# Ivy_Sensor.net
KiCad netlist of a schematic drawn in EAGLE
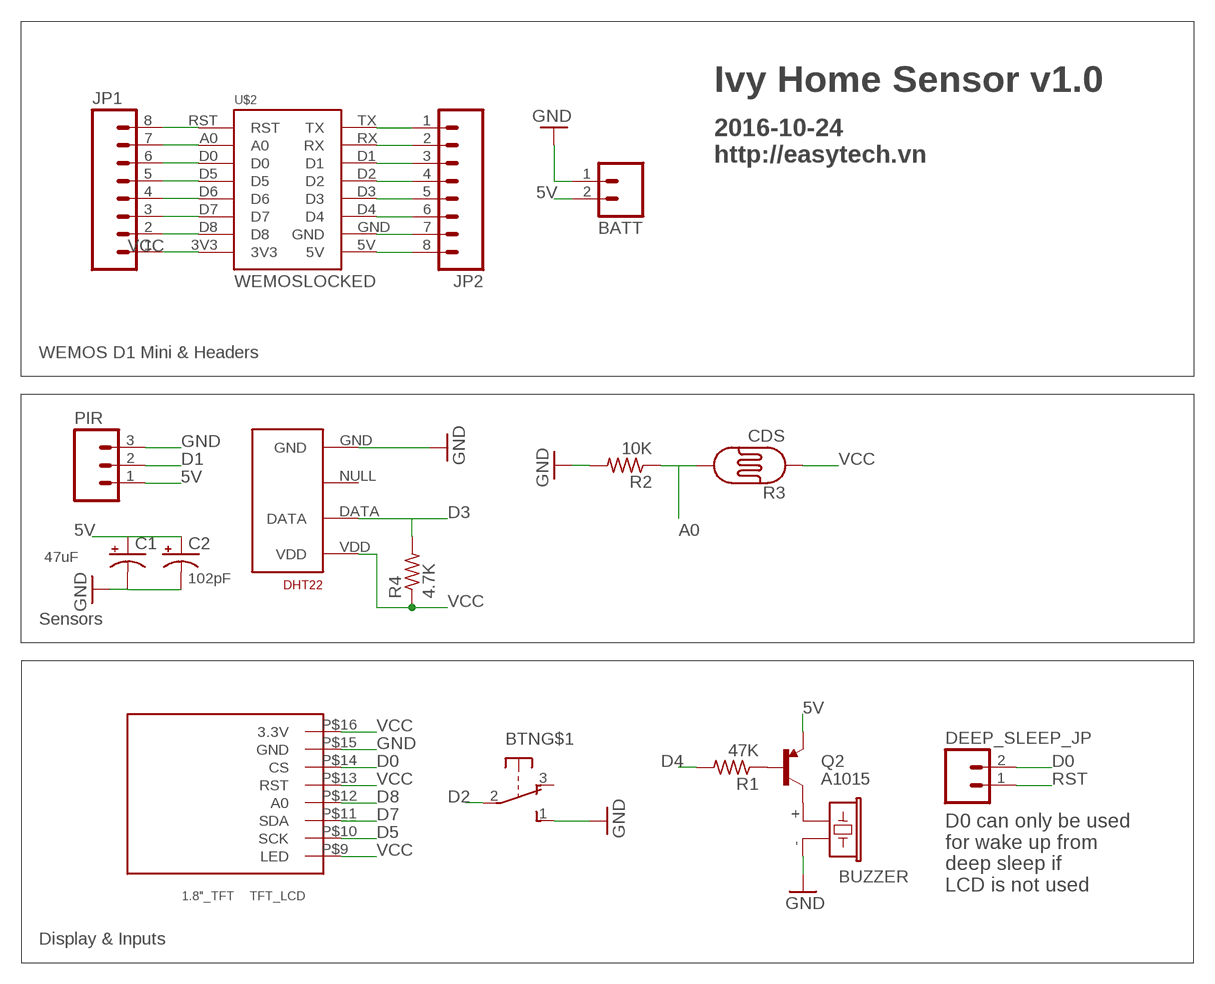
[diagram p0: schematic, sheet 1]

(export (version "E")
  (design (tool "Eeschema 10.0.6"))
  (components
    (comp (ref "BATT")
      (value "M02PTH")
      (footprint "eagle-import:1X02")
      (libsource (lib "eagle-import") (part "M02PTH"))
    )
    (comp (ref "BTN")
      (value "OS102011MA1Q")
      (footprint "eagle-import:OS102011MA1Q")
      (libsource (lib "eagle-import") (part "OS102011MA1Q"))
    )
    (comp (ref "BUZZER")
      (value "F/CM12P")
      (footprint "eagle-import:F_CM12P")
      (libsource (lib "eagle-import") (part "F/CM12P"))
    )
    (comp (ref "C1")
      (value "47uF")
      (footprint "eagle-import:CPOL-RADIAL-10UF-25V")
      (libsource (lib "eagle-import") (part "CAP_POLPTH2"))
    )
    (comp (ref "C2")
      (value "102pF")
      (footprint "eagle-import:CPOL-RADIAL-10UF-25V")
      (libsource (lib "eagle-import") (part "CAP_POLPTH2"))
    )
    (comp (ref "DEEP_SLEEP_JP")
      (value "M02PTH")
      (footprint "eagle-import:1X02")
      (libsource (lib "eagle-import") (part "M02PTH"))
    )
    (comp (ref "DHT22")
      (value "RHT03_DHT-22_AM2302RA")
      (footprint "eagle-import:RHT03_DHT-22_RA")
      (libsource (lib "eagle-import") (part "RHT03_DHT-22_AM2302RA"))
    )
    (comp (ref "JP1")
      (value "M08")
      (footprint "eagle-import:1X08_ROUND")
      (libsource (lib "eagle-import") (part "M08"))
    )
    (comp (ref "JP2")
      (value "M08")
      (footprint "eagle-import:1X08_ROUND")
      (libsource (lib "eagle-import") (part "M08"))
    )
    (comp (ref "PIR")
      (value "M03PTH")
      (footprint "eagle-import:1X03")
      (libsource (lib "eagle-import") (part "M03PTH"))
    )
    (comp (ref "Q2")
      (value "A1015")
      (footprint "eagle-import:SOT23-3")
      (libsource (lib "eagle-import") (part "TRANSISTOR_PNPSMD"))
    )
    (comp (ref "R1")
      (value "47K")
      (footprint "eagle-import:R0805")
      (libsource (lib "eagle-import") (part "R-US_R0805"))
    )
    (comp (ref "R2")
      (value "10K")
      (footprint "eagle-import:R0805")
      (libsource (lib "eagle-import") (part "R-US_R0805"))
    )
    (comp (ref "R3")
      (value "CDS")
      (footprint "eagle-import:PHOTOCELL_THIN")
      (libsource (lib "eagle-import") (part "PHOTOCELL"))
    )
    (comp (ref "R4")
      (value "4.7K")
      (footprint "eagle-import:R0805")
      (libsource (lib "eagle-import") (part "R-US_R0805"))
    )
    (comp (ref "TFT_LCD")
      (value "1.8\"_TFT")
      (footprint "eagle-import:1.8__TFT")
      (libsource (lib "eagle-import") (part "1.8{dblquote}_TFT"))
    )
    (comp (ref "U$2")
      (value "WEMOSLOCKED")
      (footprint "eagle-import:WEMOS_LOCKED")
      (libsource (lib "eagle-import") (part "WEMOSLOCKED"))
    )
  )
  (nets
    (net (code "1") (name "/5V") (class "Default")
      (node (ref "BATT") (pin "2") (pinfunction "2_2") (pintype "passive"))
      (node (ref "C1") (pin "1") (pinfunction "+_1") (pintype "passive"))
      (node (ref "C2") (pin "1") (pinfunction "+_1") (pintype "passive"))
      (node (ref "JP2") (pin "8") (pinfunction "8_8") (pintype "passive"))
      (node (ref "PIR") (pin "1") (pinfunction "1_1") (pintype "passive"))
      (node (ref "Q2") (pin "2") (pinfunction "E_2") (pintype "passive"))
      (node (ref "U$2") (pin "5V") (pinfunction "5V_5V") (pintype "bidirectional"))
    )
    (net (code "2") (name "/A0") (class "Default")
      (node (ref "JP1") (pin "7") (pinfunction "7_7") (pintype "passive"))
      (node (ref "R2") (pin "1") (pinfunction "1_1") (pintype "passive"))
      (node (ref "R3") (pin "2") (pinfunction "P$2_2") (pintype "bidirectional"))
      (node (ref "U$2") (pin "A0") (pinfunction "A0_A0") (pintype "bidirectional"))
    )
    (net (code "3") (name "/D0") (class "Default")
      (node (ref "DEEP_SLEEP_JP") (pin "2") (pinfunction "2_2") (pintype "passive"))
      (node (ref "JP1") (pin "6") (pinfunction "6_6") (pintype "passive"))
      (node (ref "TFT_LCD") (pin "P$14") (pinfunction "CS_P$14") (pintype "bidirectional"))
      (node (ref "U$2") (pin "D0") (pinfunction "D0_D0") (pintype "bidirectional"))
    )
    (net (code "4") (name "/D1") (class "Default")
      (node (ref "JP2") (pin "3") (pinfunction "3_3") (pintype "passive"))
      (node (ref "PIR") (pin "2") (pinfunction "2_2") (pintype "passive"))
      (node (ref "U$2") (pin "D1") (pinfunction "D1_D1") (pintype "bidirectional"))
    )
    (net (code "5") (name "/D2") (class "Default")
      (node (ref "BTN") (pin "2") (pinfunction "P_2") (pintype "passive"))
      (node (ref "JP2") (pin "4") (pinfunction "4_4") (pintype "passive"))
      (node (ref "U$2") (pin "D2") (pinfunction "D2_D2") (pintype "bidirectional"))
    )
    (net (code "6") (name "/D3") (class "Default")
      (node (ref "DHT22") (pin "DATA") (pinfunction "DATA_DATA") (pintype "bidirectional"))
      (node (ref "JP2") (pin "5") (pinfunction "5_5") (pintype "passive"))
      (node (ref "R4") (pin "2") (pinfunction "2_2") (pintype "passive"))
      (node (ref "U$2") (pin "D3") (pinfunction "D3_D3") (pintype "bidirectional"))
    )
    (net (code "7") (name "/D4") (class "Default")
      (node (ref "JP2") (pin "6") (pinfunction "6_6") (pintype "passive"))
      (node (ref "R1") (pin "2") (pinfunction "2_2") (pintype "passive"))
      (node (ref "U$2") (pin "D4") (pinfunction "D4_D4") (pintype "bidirectional"))
    )
    (net (code "8") (name "/D5") (class "Default")
      (node (ref "JP1") (pin "5") (pinfunction "5_5") (pintype "passive"))
      (node (ref "TFT_LCD") (pin "P$10") (pinfunction "SCK_P$10") (pintype "bidirectional"))
      (node (ref "U$2") (pin "D5") (pinfunction "D5_D5") (pintype "bidirectional"))
    )
    (net (code "9") (name "/D7") (class "Default")
      (node (ref "JP1") (pin "3") (pinfunction "3_3") (pintype "passive"))
      (node (ref "TFT_LCD") (pin "P$11") (pinfunction "SDA_P$11") (pintype "bidirectional"))
      (node (ref "U$2") (pin "D7") (pinfunction "D7_D7") (pintype "bidirectional"))
    )
    (net (code "10") (name "/D8") (class "Default")
      (node (ref "JP1") (pin "2") (pinfunction "2_2") (pintype "passive"))
      (node (ref "TFT_LCD") (pin "P$12") (pinfunction "A0_P$12") (pintype "bidirectional"))
      (node (ref "U$2") (pin "D8") (pinfunction "D8_D8") (pintype "bidirectional"))
    )
    (net (code "11") (name "/RST") (class "Default")
      (node (ref "DEEP_SLEEP_JP") (pin "1") (pinfunction "1_1") (pintype "passive"))
      (node (ref "JP1") (pin "8") (pinfunction "8_8") (pintype "passive"))
      (node (ref "U$2") (pin "RST") (pinfunction "RST_RST") (pintype "bidirectional"))
    )
    (net (code "12") (name "/VCC") (class "Default")
      (node (ref "DHT22") (pin "VDD") (pinfunction "VDD_VDD") (pintype "power_in"))
      (node (ref "JP1") (pin "1") (pinfunction "1_1") (pintype "passive"))
      (node (ref "R3") (pin "1") (pinfunction "P$1_1") (pintype "bidirectional"))
      (node (ref "R4") (pin "1") (pinfunction "1_1") (pintype "passive"))
      (node (ref "TFT_LCD") (pin "P$13") (pinfunction "RST_P$13") (pintype "bidirectional"))
      (node (ref "TFT_LCD") (pin "P$16") (pinfunction "3.3V_P$16") (pintype "bidirectional"))
      (node (ref "TFT_LCD") (pin "P$9") (pinfunction "LED_P$9") (pintype "bidirectional"))
      (node (ref "U$2") (pin "3V3") (pinfunction "3V3_3V3") (pintype "bidirectional"))
    )
    (net (code "13") (name "GND") (class "Default")
      (node (ref "BATT") (pin "1") (pinfunction "1_1") (pintype "passive"))
      (node (ref "BTN") (pin "1") (pinfunction "S_1") (pintype "passive"))
      (node (ref "BUZZER") (pin "-") (pinfunction "2_-") (pintype "passive"))
      (node (ref "C1") (pin "2") (pinfunction "-_2") (pintype "passive"))
      (node (ref "C2") (pin "2") (pinfunction "-_2") (pintype "passive"))
      (node (ref "DHT22") (pin "GND") (pinfunction "GND_GND") (pintype "power_in"))
      (node (ref "JP2") (pin "7") (pinfunction "7_7") (pintype "passive"))
      (node (ref "PIR") (pin "3") (pinfunction "3_3") (pintype "passive"))
      (node (ref "R2") (pin "2") (pinfunction "2_2") (pintype "passive"))
      (node (ref "TFT_LCD") (pin "P$15") (pinfunction "GND_P$15") (pintype "bidirectional"))
      (node (ref "U$2") (pin "GND") (pinfunction "GND_GND") (pintype "bidirectional"))
    )
    (net (code "14") (name "Net-(BUZZER-1)") (class "Default")
      (node (ref "BUZZER") (pin "+") (pinfunction "1_+") (pintype "passive"))
      (node (ref "Q2") (pin "3") (pinfunction "C_3") (pintype "passive"))
    )
    (net (code "15") (name "Net-(JP1-Pad4)") (class "Default")
      (node (ref "JP1") (pin "4") (pinfunction "4_4") (pintype "passive"))
      (node (ref "U$2") (pin "D6") (pinfunction "D6_D6") (pintype "bidirectional"))
    )
    (net (code "16") (name "Net-(JP2-Pad1)") (class "Default")
      (node (ref "JP2") (pin "1") (pinfunction "1_1") (pintype "passive"))
      (node (ref "U$2") (pin "TX") (pinfunction "TX_TX") (pintype "bidirectional"))
    )
    (net (code "17") (name "Net-(JP2-Pad2)") (class "Default")
      (node (ref "JP2") (pin "2") (pinfunction "2_2") (pintype "passive"))
      (node (ref "U$2") (pin "RX") (pinfunction "RX_RX") (pintype "bidirectional"))
    )
    (net (code "18") (name "Net-(Q2-B)") (class "Default")
      (node (ref "Q2") (pin "1") (pinfunction "B_1") (pintype "passive"))
      (node (ref "R1") (pin "1") (pinfunction "1_1") (pintype "passive"))
    )
    (net (code "19") (name "unconnected-(BTNA-O-Pad3)") (class "Default")
      (node (ref "BTN") (pin "3") (pinfunction "O_3") (pintype "passive"))
    )
    (net (code "20") (name "unconnected-(DHT22-PadNULL)") (class "Default")
      (node (ref "DHT22") (pin "NULL") (pinfunction "NULL_NULL") (pintype "no_connect"))
    )
  )
)
